# 0_Top.net
KiCad netlist of a schematic drawn in Altium Designer
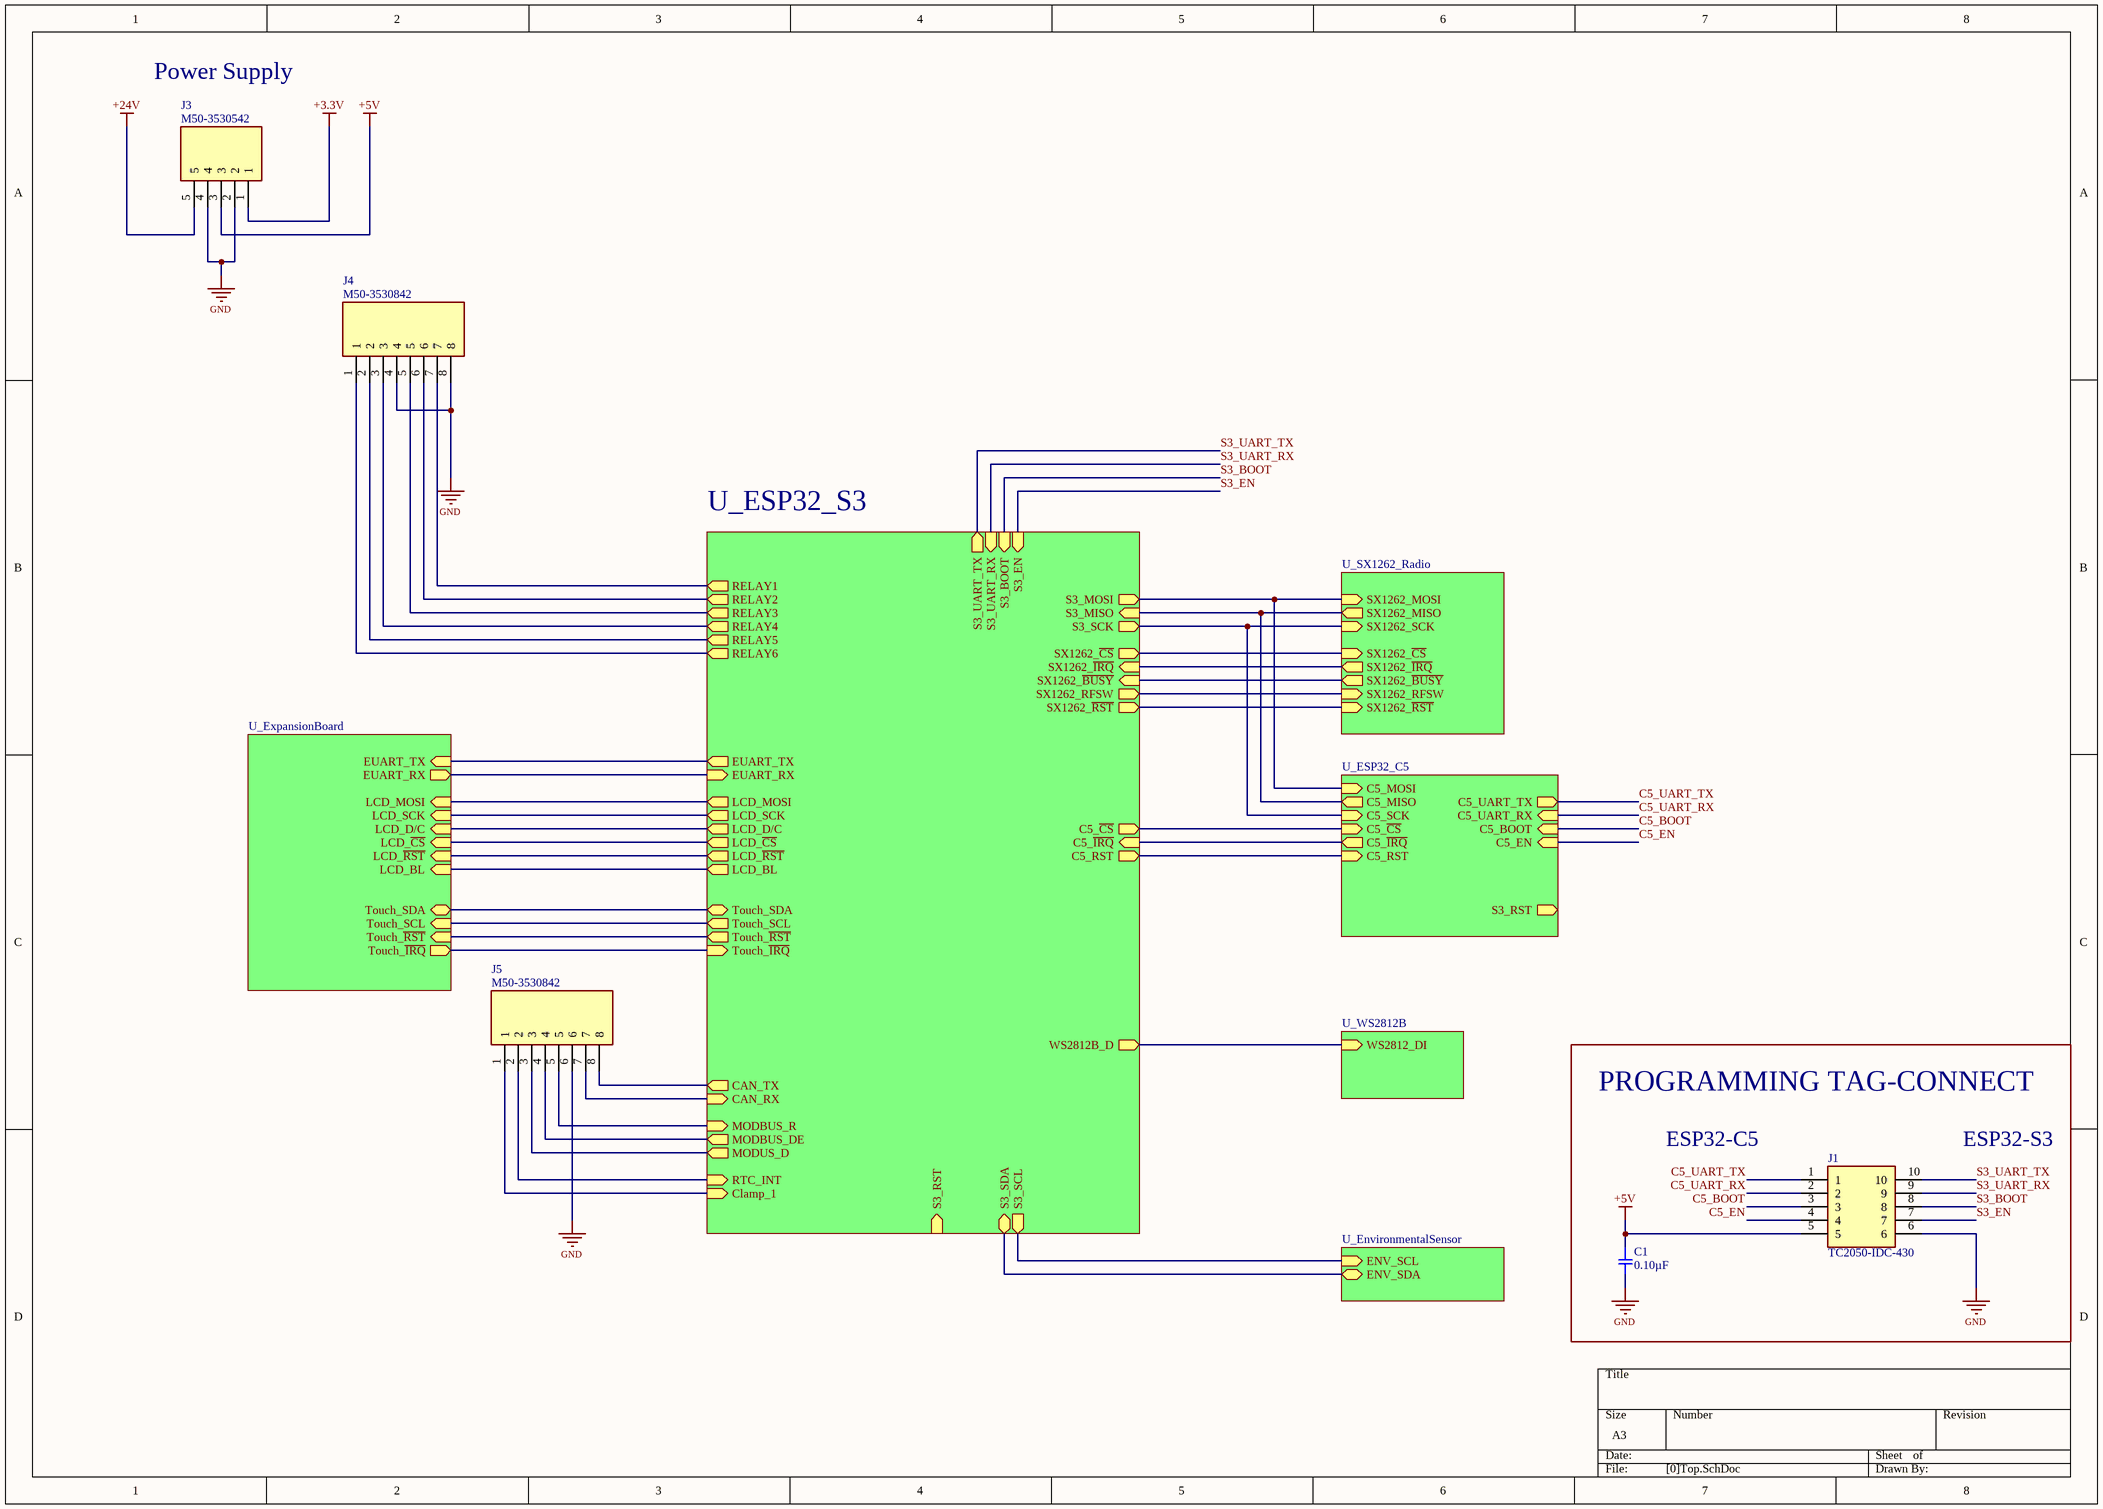
[diagram p0: [0]Top.SchDoc]

(export (version "E")
  (design (tool "Eeschema 10.0.6"))
  (components
    (comp (ref "C1")
      (value "0.10µF")
      (footprint "SMD-0402C")
      (description "CAP CER 0.1UF 16V X7R 0402")
      (fields
        (field (name "DIGI-KEY PART NUMBER") "490-4759-1-ND")
        (field (name "PART NUMBER") "GCM155R71C104KA55D")
      )
      (libsource (lib "capacitor_murata_0402") (part "GCM155R71C104KA55D"))
    )
    (comp (ref "J1")
      (value "TC2050-IDC-430")
      (footprint "SamacSys:TC2050-IDC")
      (description "Connector")
      (libsource (lib "*") (part "TC2050-IDC-430"))
    )
    (comp (ref "J3")
      (value "M50-3530542")
      (footprint "SamacSys:HDRV5W40P0X127_1X5_635X210X400P")
      (description "Connector")
      (fields (field (name "MOUSER PART NUMBER") "855-M50-3530542"))
      (libsource (lib "*") (part "M50-3530542"))
    )
    (comp (ref "J4")
      (value "M50-3530842")
      (footprint "SamacSys:HDRV8W40P0X127_1X8_1016X210X400P")
      (description "Connector")
      (fields (field (name "MOUSER PART NUMBER") "855-M50-3530842"))
      (libsource (lib "*") (part "M50-3530842"))
    )
    (comp (ref "J5")
      (value "M50-3530842")
      (footprint "SamacSys:HDRV8W40P0X127_1X8_1016X210X400P")
      (description "Connector")
      (fields (field (name "MOUSER PART NUMBER") "855-M50-3530842"))
      (libsource (lib "*") (part "M50-3530842"))
    )
  )
  (nets
    (net (code "1") (name "+3.3V") (class "Default")
      (node (ref "J3") (pin "1") (pinfunction "1_1") (pintype "passive"))
    )
    (net (code "2") (name "+5V") (class "Default")
      (node (ref "C1") (pin "1") (pinfunction "1_1") (pintype "passive"))
      (node (ref "J1") (pin "5") (pinfunction "5_5") (pintype "passive"))
      (node (ref "J3") (pin "3") (pinfunction "3_3") (pintype "passive"))
    )
    (net (code "3") (name "+24V") (class "Default")
      (node (ref "J3") (pin "5") (pinfunction "5_5") (pintype "passive"))
    )
    (net (code "4") (name "/C5_BOOT") (class "Default")
      (node (ref "J1") (pin "3") (pinfunction "3_3") (pintype "passive"))
    )
    (net (code "5") (name "/C5_EN") (class "Default")
      (node (ref "J1") (pin "4") (pinfunction "4_4") (pintype "passive"))
    )
    (net (code "8") (name "/C5_UART_RX") (class "Default")
      (node (ref "J1") (pin "2") (pinfunction "2_2") (pintype "passive"))
    )
    (net (code "9") (name "/C5_UART_TX") (class "Default")
      (node (ref "J1") (pin "1") (pinfunction "1_1") (pintype "passive"))
    )
    (net (code "12") (name "/CAN_RX") (class "Default")
      (node (ref "J5") (pin "7") (pinfunction "7_7") (pintype "passive"))
    )
    (net (code "13") (name "/CAN_TX") (class "Default")
      (node (ref "J5") (pin "8") (pinfunction "8_8") (pintype "passive"))
    )
    (net (code "14") (name "/Clamp_1") (class "Default")
      (node (ref "J5") (pin "1") (pinfunction "1_1") (pintype "passive"))
    )
    (net (code "24") (name "/MODBUS_DE") (class "Default")
      (node (ref "J5") (pin "4") (pinfunction "4_4") (pintype "passive"))
    )
    (net (code "25") (name "/MODBUS_R") (class "Default")
      (node (ref "J5") (pin "5") (pinfunction "5_5") (pintype "passive"))
    )
    (net (code "26") (name "/MODUS_D") (class "Default")
      (node (ref "J5") (pin "3") (pinfunction "3_3") (pintype "passive"))
    )
    (net (code "27") (name "/RELAY1") (class "Default")
      (node (ref "J4") (pin "7") (pinfunction "7_7") (pintype "passive"))
    )
    (net (code "28") (name "/RELAY2") (class "Default")
      (node (ref "J4") (pin "6") (pinfunction "6_6") (pintype "passive"))
    )
    (net (code "29") (name "/RELAY3") (class "Default")
      (node (ref "J4") (pin "5") (pinfunction "5_5") (pintype "passive"))
    )
    (net (code "30") (name "/RELAY4") (class "Default")
      (node (ref "J4") (pin "3") (pinfunction "3_3") (pintype "passive"))
    )
    (net (code "31") (name "/RELAY5") (class "Default")
      (node (ref "J4") (pin "2") (pinfunction "2_2") (pintype "passive"))
    )
    (net (code "32") (name "/RELAY6") (class "Default")
      (node (ref "J4") (pin "1") (pinfunction "1_1") (pintype "passive"))
    )
    (net (code "33") (name "/RTC_INT") (class "Default")
      (node (ref "J5") (pin "2") (pinfunction "2_2") (pintype "passive"))
    )
    (net (code "34") (name "/S3_BOOT") (class "Default")
      (node (ref "J1") (pin "8") (pinfunction "8_8") (pintype "passive"))
    )
    (net (code "35") (name "/S3_EN") (class "Default")
      (node (ref "J1") (pin "7") (pinfunction "7_7") (pintype "passive"))
    )
    (net (code "41") (name "/S3_UART_RX") (class "Default")
      (node (ref "J1") (pin "9") (pinfunction "9_9") (pintype "passive"))
    )
    (net (code "42") (name "/S3_UART_TX") (class "Default")
      (node (ref "J1") (pin "10") (pinfunction "10_10") (pintype "passive"))
    )
    (net (code "53") (name "GND") (class "Default")
      (node (ref "C1") (pin "2") (pinfunction "2_2") (pintype "passive"))
      (node (ref "J1") (pin "6") (pinfunction "6_6") (pintype "passive"))
      (node (ref "J3") (pin "2") (pinfunction "2_2") (pintype "passive"))
      (node (ref "J3") (pin "4") (pinfunction "4_4") (pintype "passive"))
      (node (ref "J4") (pin "4") (pinfunction "4_4") (pintype "passive"))
      (node (ref "J4") (pin "8") (pinfunction "8_8") (pintype "passive"))
      (node (ref "J5") (pin "6") (pinfunction "6_6") (pintype "passive"))
    )
  )
)
